# MinieasySens-RS485_V12-Build020.net
KiCad netlist of a schematic drawn in EAGLE
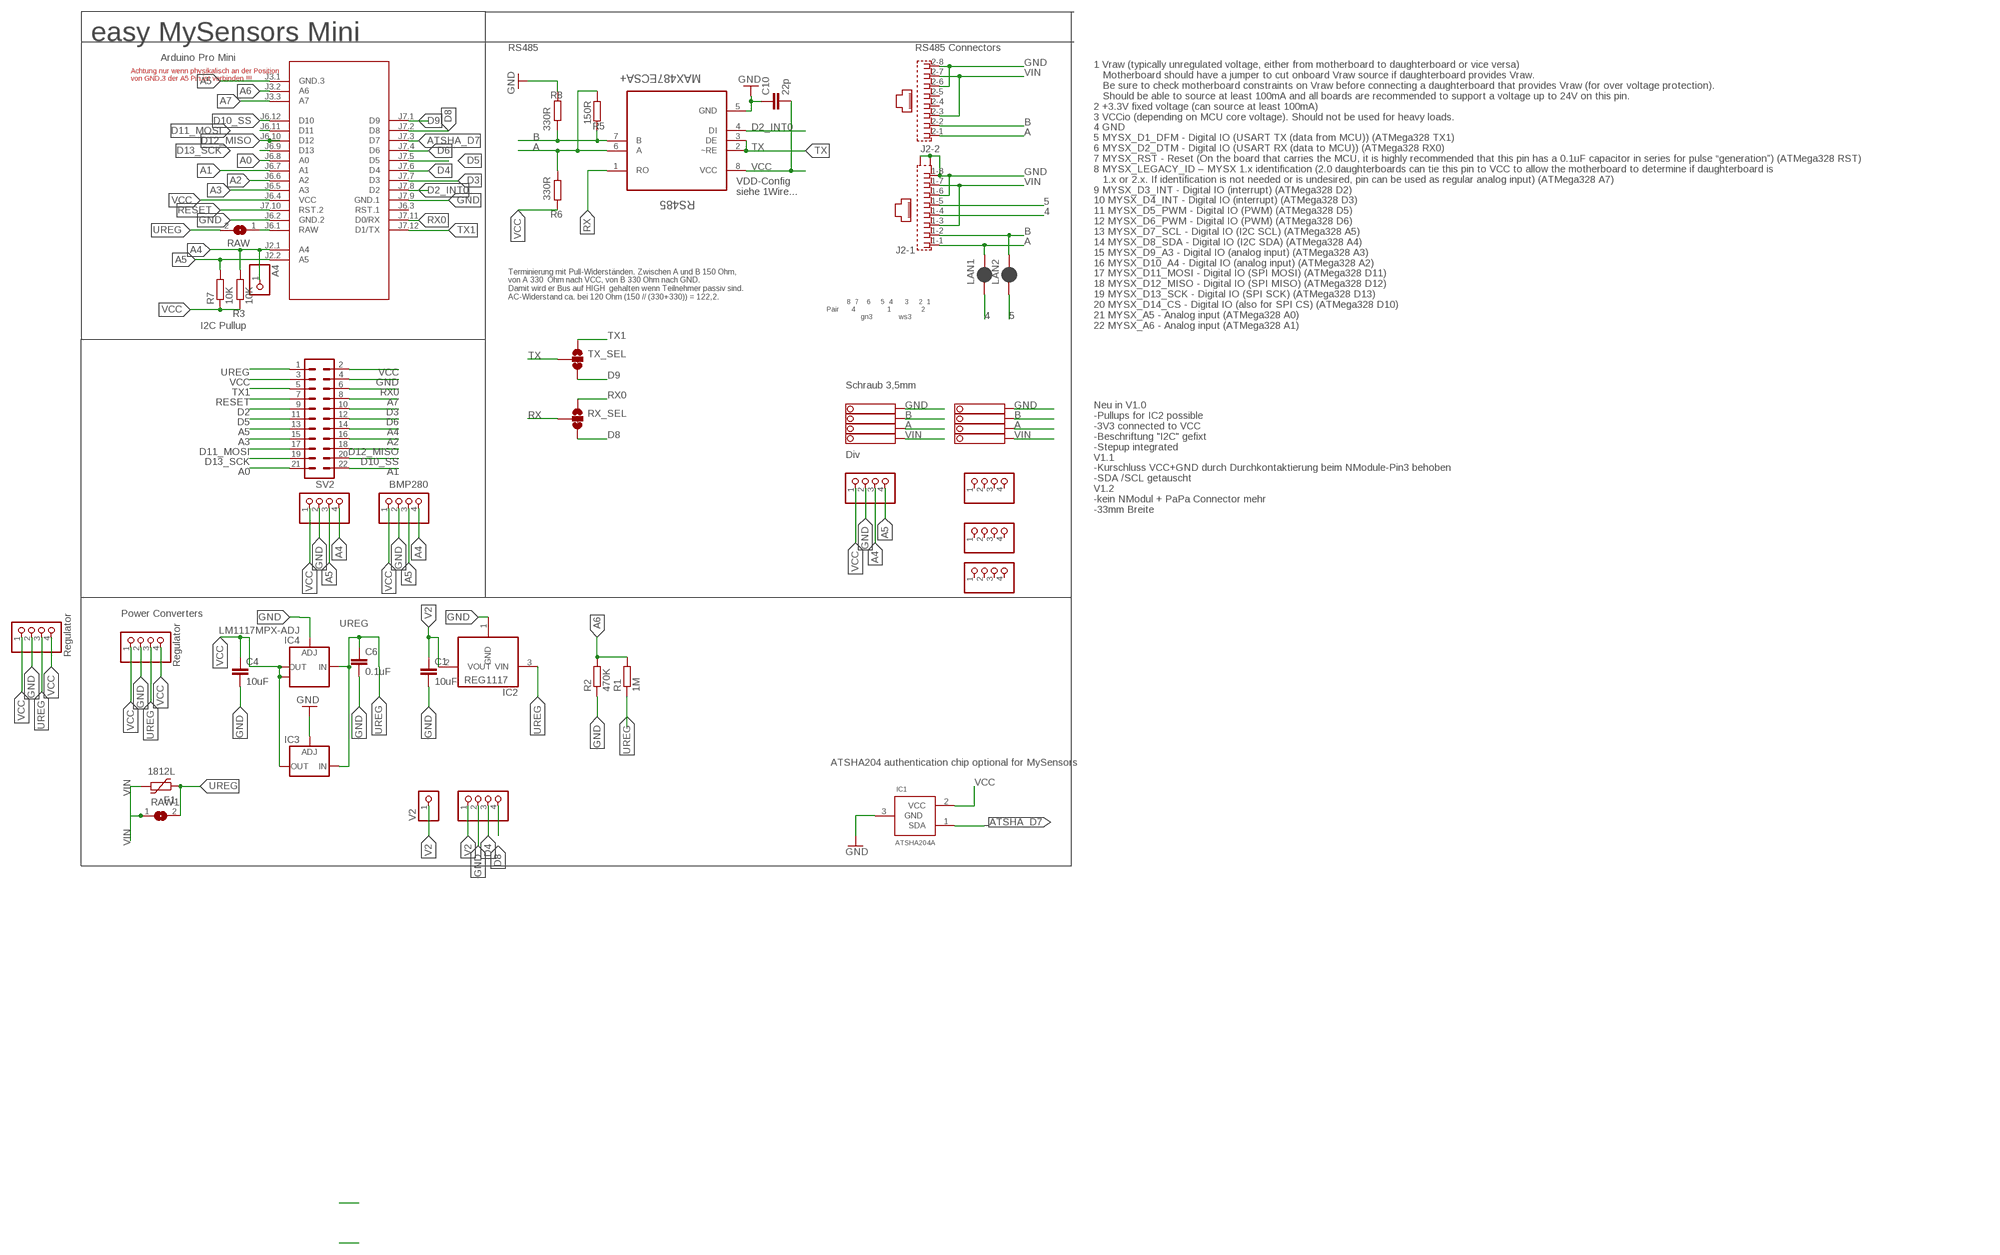
[diagram p0: schematic, sheet 1]

(export (version "E")
  (design (tool "Eeschema 10.0.6"))
  (components
    (comp (ref "A4")
      (value "PINHD-1X1")
      (footprint "eagle-import:1X01")
      (libsource (lib "eagle-import") (part "PINHD-1X1"))
    )
    (comp (ref "BH1750")
      (value "PINHD-1X04_2.54-S")
      (footprint "eagle-import:1X04-S")
      (libsource (lib "eagle-import") (part "PINHD-1X04_2.54-S"))
    )
    (comp (ref "C1")
      (value "10uF")
      (footprint "eagle-import:C1210")
      (libsource (lib "eagle-import") (part "C-EUC1210"))
    )
    (comp (ref "C4")
      (value "10uF")
      (footprint "eagle-import:C1210")
      (libsource (lib "eagle-import") (part "C-EUC1210"))
    )
    (comp (ref "C6")
      (value "0.1uF")
      (footprint "eagle-import:C1206")
      (libsource (lib "eagle-import") (part "C-EUC1206"))
    )
    (comp (ref "C10")
      (value "22p")
      (footprint "eagle-import:C0805")
      (libsource (lib "eagle-import") (part "C-EUC0805"))
    )
    (comp (ref "F1")
      (value "1812L")
      (footprint "eagle-import:1812L")
      (libsource (lib "eagle-import") (part "1812L"))
    )
    (comp (ref "I2C-1")
      (value "PINHD-1X04_2.54-S")
      (footprint "eagle-import:1X04-S")
      (libsource (lib "eagle-import") (part "PINHD-1X04_2.54-S"))
    )
    (comp (ref "I2C-2")
      (value "PINHD-1X04_2.54-S")
      (footprint "eagle-import:1X04-S")
      (libsource (lib "eagle-import") (part "PINHD-1X04_2.54-S"))
    )
    (comp (ref "IC1")
      (value "ATSHA204A")
      (footprint "eagle-import:SOT23")
      (libsource (lib "eagle-import") (part "ATSHA204A"))
    )
    (comp (ref "IC2")
      (value "REG1117")
      (footprint "eagle-import:SOT223")
      (libsource (lib "eagle-import") (part "REG1117"))
    )
    (comp (ref "IC3")
      (value "LD117ADT50TR")
      (footprint "eagle-import:DPACK")
      (libsource (lib "eagle-import") (part "LD117A?DT50TR"))
    )
    (comp (ref "IC4")
      (value "LM1117MPX-ADJ")
      (footprint "eagle-import:SOT223")
      (libsource (lib "eagle-import") (part "LM1117MPX-ADJ"))
    )
    (comp (ref "J2")
      (value "RJ45_2X_NARROW_SHILDPINS_NOCASE")
      (footprint "eagle-import:RJ45_2X_NARROW_SHILDPINS_NOCASE")
      (libsource (lib "eagle-import") (part "RJ45_2X_NARROW_SHILDPINS_NOCASE"))
    )
    (comp (ref "JP1")
      (value "PINHD-1X04_2.54-S")
      (footprint "eagle-import:1X04-S")
      (libsource (lib "eagle-import") (part "PINHD-1X04_2.54-S"))
    )
    (comp (ref "JP2")
      (value "PINHD-1X04_2.54-S")
      (footprint "eagle-import:1X04-S")
      (libsource (lib "eagle-import") (part "PINHD-1X04_2.54-S"))
    )
    (comp (ref "JP4")
      (value "PINHD-1X04_2.54-S")
      (footprint "eagle-import:1X04-S")
      (libsource (lib "eagle-import") (part "PINHD-1X04_2.54-S"))
    )
    (comp (ref "LAN1")
      (value "JUMPER-SMT_2_NC_PASTE_SILK")
      (footprint "eagle-import:SMT-JUMPER_2_NC_PASTE_SILK")
      (libsource (lib "eagle-import") (part "JUMPER-SMT_2_NC_PASTE_SILK"))
    )
    (comp (ref "LAN2")
      (value "JUMPER-SMT_2_NC_PASTE_SILK")
      (footprint "eagle-import:SMT-JUMPER_2_NC_PASTE_SILK")
      (libsource (lib "eagle-import") (part "JUMPER-SMT_2_NC_PASTE_SILK"))
    )
    (comp (ref "M1")
      (value "ARDUINO-PRO-MINI-3.3V#NP")
      (footprint "eagle-import:ARDUINO-PRO-MINI#NP")
      (libsource (lib "eagle-import") (part "ARDUINO-PRO-MINI-#NP3.3V"))
    )
    (comp (ref "R1")
      (value "1M")
      (footprint "eagle-import:R0805")
      (libsource (lib "eagle-import") (part "R-EU_R0805"))
    )
    (comp (ref "R2")
      (value "470K")
      (footprint "eagle-import:R0805")
      (libsource (lib "eagle-import") (part "R-EU_R0805"))
    )
    (comp (ref "R3")
      (value "10K")
      (footprint "eagle-import:R0805")
      (libsource (lib "eagle-import") (part "R-EU_R0805"))
    )
    (comp (ref "R5")
      (value "150R")
      (footprint "eagle-import:R0805")
      (libsource (lib "eagle-import") (part "R-EU_R0805"))
    )
    (comp (ref "R6")
      (value "330R")
      (footprint "eagle-import:R0805")
      (libsource (lib "eagle-import") (part "R-EU_R0805"))
    )
    (comp (ref "R7")
      (value "10K")
      (footprint "eagle-import:R0805")
      (libsource (lib "eagle-import") (part "R-EU_R0805"))
    )
    (comp (ref "R8")
      (value "330R")
      (footprint "eagle-import:R0805")
      (libsource (lib "eagle-import") (part "R-EU_R0805"))
    )
    (comp (ref "RAW") (value "SJ") (footprint "eagle-import:SJ") (libsource (lib "eagle-import") (part "SJ")))
    (comp (ref "RAW1")
      (value "SJ")
      (footprint "eagle-import:SJ")
      (libsource (lib "eagle-import") (part "SJ"))
    )
    (comp (ref "RS485")
      (value "MAX487ECSA+")
      (footprint "eagle-import:SOIC127P600X175-8N")
      (libsource (lib "eagle-import") (part "MAX487ECSA+"))
    )
    (comp (ref "RX_SEL")
      (value "JUMPER-SMT_3_1-NC_TRACE_SILK")
      (footprint "eagle-import:SMT-JUMPER_3_1-NC_TRACE_SILK")
      (libsource (lib "eagle-import") (part "JUMPER-SMT_3_1-NC_TRACE_SILK"))
    )
    (comp (ref "STEPDWN")
      (value "PINHD-1X04_2.54-S")
      (footprint "eagle-import:1X04-S")
      (libsource (lib "eagle-import") (part "PINHD-1X04_2.54-S"))
    )
    (comp (ref "STEPDWN1")
      (value "PINHD-1X04_2.54-S")
      (footprint "eagle-import:1X04-S")
      (libsource (lib "eagle-import") (part "PINHD-1X04_2.54-S"))
    )
    (comp (ref "SV2")
      (value "MA11-2")
      (footprint "eagle-import:MA11-2")
      (libsource (lib "eagle-import") (part "MA11-2"))
    )
    (comp (ref "TX_SEL")
      (value "JUMPER-SMT_3_1-NC_TRACE_SILK")
      (footprint "eagle-import:SMT-JUMPER_3_1-NC_TRACE_SILK")
      (libsource (lib "eagle-import") (part "JUMPER-SMT_3_1-NC_TRACE_SILK"))
    )
    (comp (ref "V2")
      (value "PINHD-1X1")
      (footprint "eagle-import:1X01")
      (libsource (lib "eagle-import") (part "PINHD-1X1"))
    )
    (comp (ref "V2-")
      (value "PINHD-1X04_2.54-S")
      (footprint "eagle-import:1X04-S")
      (libsource (lib "eagle-import") (part "PINHD-1X04_2.54-S"))
    )
    (comp (ref "X1")
      (value "1751264")
      (footprint "eagle-import:1751264")
      (libsource (lib "eagle-import") (part "1751264"))
    )
    (comp (ref "X4")
      (value "1751264")
      (footprint "eagle-import:1751264")
      (libsource (lib "eagle-import") (part "1751264"))
    )
  )
  (nets
    (net (code "1") (name "/4") (class "Default")
      (node (ref "J2") (pin "1-4") (pinfunction "4_1-4") (pintype "passive"))
      (node (ref "LAN1") (pin "1") (pinfunction "1_1") (pintype "passive"))
    )
    (net (code "2") (name "/5") (class "Default")
      (node (ref "J2") (pin "1-5") (pinfunction "5_1-5") (pintype "passive"))
      (node (ref "LAN2") (pin "1") (pinfunction "1_1") (pintype "passive"))
    )
    (net (code "3") (name "/A") (class "Default")
      (node (ref "J2") (pin "1-1") (pinfunction "1_1-1") (pintype "passive"))
      (node (ref "J2") (pin "2-1") (pinfunction "1_2-1") (pintype "passive"))
      (node (ref "LAN1") (pin "2") (pinfunction "2_2") (pintype "passive"))
      (node (ref "R5") (pin "1") (pinfunction "1_1") (pintype "passive"))
      (node (ref "R6") (pin "2") (pinfunction "2_2") (pintype "passive"))
      (node (ref "RS485") (pin "6") (pinfunction "A_6") (pintype "bidirectional"))
      (node (ref "X1") (pin "2") (pinfunction "K_2") (pintype "passive"))
      (node (ref "X4") (pin "2") (pinfunction "K_2") (pintype "passive"))
    )
    (net (code "4") (name "/B") (class "Default")
      (node (ref "J2") (pin "1-2") (pinfunction "2_1-2") (pintype "passive"))
      (node (ref "J2") (pin "2-2") (pinfunction "2_2-2") (pintype "passive"))
      (node (ref "LAN2") (pin "2") (pinfunction "2_2") (pintype "passive"))
      (node (ref "R5") (pin "2") (pinfunction "2_2") (pintype "passive"))
      (node (ref "R8") (pin "1") (pinfunction "1_1") (pintype "passive"))
      (node (ref "RS485") (pin "7") (pinfunction "B_7") (pintype "bidirectional"))
      (node (ref "X1") (pin "3") (pinfunction "K_3") (pintype "passive"))
      (node (ref "X4") (pin "3") (pinfunction "K_3") (pintype "passive"))
    )
    (net (code "5") (name "/D2") (class "Default")
      (node (ref "SV2") (pin "9") (pinfunction "9_9") (pintype "passive"))
    )
    (net (code "6") (name "/VIN") (class "Default")
      (node (ref "F1") (pin "P$2") (pinfunction "2_P$2") (pintype "passive"))
      (node (ref "J2") (pin "1-3") (pinfunction "3_1-3") (pintype "passive"))
      (node (ref "J2") (pin "1-7") (pinfunction "7_1-7") (pintype "passive"))
      (node (ref "J2") (pin "2-3") (pinfunction "3_2-3") (pintype "passive"))
      (node (ref "J2") (pin "2-7") (pinfunction "7_2-7") (pintype "passive"))
      (node (ref "RAW1") (pin "1") (pinfunction "1_1") (pintype "passive"))
      (node (ref "X1") (pin "1") (pinfunction "K_1") (pintype "passive"))
      (node (ref "X4") (pin "1") (pinfunction "K_1") (pintype "passive"))
    )
    (net (code "7") (name "A0") (class "Default")
      (node (ref "M1") (pin "J6.8") (pinfunction "A0_J6.8") (pintype "bidirectional"))
      (node (ref "SV2") (pin "21") (pinfunction "21_21") (pintype "passive"))
    )
    (net (code "8") (name "A1") (class "Default")
      (node (ref "M1") (pin "J6.7") (pinfunction "A1_J6.7") (pintype "bidirectional"))
      (node (ref "SV2") (pin "22") (pinfunction "22_22") (pintype "passive"))
    )
    (net (code "9") (name "A2") (class "Default")
      (node (ref "M1") (pin "J6.6") (pinfunction "A2_J6.6") (pintype "bidirectional"))
      (node (ref "SV2") (pin "16") (pinfunction "16_16") (pintype "passive"))
    )
    (net (code "10") (name "A3") (class "Default")
      (node (ref "M1") (pin "J6.5") (pinfunction "A3_J6.5") (pintype "bidirectional"))
      (node (ref "SV2") (pin "15") (pinfunction "15_15") (pintype "passive"))
    )
    (net (code "11") (name "A4") (class "Default")
      (node (ref "A4") (pin "1") (pinfunction "1_1") (pintype "passive"))
      (node (ref "BH1750") (pin "4") (pinfunction "4_4") (pintype "passive"))
      (node (ref "I2C-1") (pin "4") (pinfunction "4_4") (pintype "passive"))
      (node (ref "I2C-2") (pin "3") (pinfunction "3_3") (pintype "passive"))
      (node (ref "M1") (pin "J2.1") (pinfunction "A4_J2.1") (pintype "bidirectional"))
      (node (ref "R3") (pin "2") (pinfunction "2_2") (pintype "passive"))
      (node (ref "SV2") (pin "14") (pinfunction "14_14") (pintype "passive"))
    )
    (net (code "12") (name "A5") (class "Default")
      (node (ref "BH1750") (pin "3") (pinfunction "3_3") (pintype "passive"))
      (node (ref "I2C-1") (pin "3") (pinfunction "3_3") (pintype "passive"))
      (node (ref "I2C-2") (pin "4") (pinfunction "4_4") (pintype "passive"))
      (node (ref "M1") (pin "J2.2") (pinfunction "A5_J2.2") (pintype "bidirectional"))
      (node (ref "M1") (pin "J3.1") (pinfunction "GND.3_J3.1") (pintype "bidirectional"))
      (node (ref "R7") (pin "2") (pinfunction "2_2") (pintype "passive"))
      (node (ref "SV2") (pin "13") (pinfunction "13_13") (pintype "passive"))
    )
    (net (code "13") (name "A6") (class "Default")
      (node (ref "M1") (pin "J3.2") (pinfunction "A6_J3.2") (pintype "bidirectional"))
      (node (ref "R1") (pin "2") (pinfunction "2_2") (pintype "passive"))
      (node (ref "R2") (pin "2") (pinfunction "2_2") (pintype "passive"))
    )
    (net (code "14") (name "A7") (class "Default")
      (node (ref "M1") (pin "J3.3") (pinfunction "A7_J3.3") (pintype "bidirectional"))
      (node (ref "SV2") (pin "8") (pinfunction "8_8") (pintype "passive"))
    )
    (net (code "15") (name "ATSHA_D7") (class "Default")
      (node (ref "IC1") (pin "1") (pinfunction "SDA_1") (pintype "bidirectional"))
      (node (ref "M1") (pin "J7.3") (pinfunction "D7_J7.3") (pintype "bidirectional"))
    )
    (net (code "16") (name "D2_INT0") (class "Default")
      (node (ref "M1") (pin "J7.8") (pinfunction "D2_J7.8") (pintype "bidirectional"))
      (node (ref "RS485") (pin "4") (pinfunction "DI_4") (pintype "input"))
    )
    (net (code "17") (name "D3") (class "Default")
      (node (ref "M1") (pin "J7.7") (pinfunction "D3_J7.7") (pintype "bidirectional"))
      (node (ref "SV2") (pin "10") (pinfunction "10_10") (pintype "passive"))
    )
    (net (code "18") (name "D4") (class "Default")
      (node (ref "M1") (pin "J7.6") (pinfunction "D4_J7.6") (pintype "bidirectional"))
      (node (ref "V2-") (pin "3") (pinfunction "3_3") (pintype "passive"))
    )
    (net (code "19") (name "D5") (class "Default")
      (node (ref "M1") (pin "J7.5") (pinfunction "D5_J7.5") (pintype "bidirectional"))
      (node (ref "SV2") (pin "11") (pinfunction "11_11") (pintype "passive"))
    )
    (net (code "20") (name "D6") (class "Default")
      (node (ref "M1") (pin "J7.4") (pinfunction "D6_J7.4") (pintype "bidirectional"))
      (node (ref "SV2") (pin "12") (pinfunction "12_12") (pintype "passive"))
    )
    (net (code "21") (name "D8") (class "Default")
      (node (ref "M1") (pin "J7.2") (pinfunction "D8_J7.2") (pintype "bidirectional"))
      (node (ref "RX_SEL") (pin "3") (pinfunction "3_3") (pintype "passive"))
      (node (ref "V2-") (pin "4") (pinfunction "4_4") (pintype "passive"))
    )
    (net (code "22") (name "D9") (class "Default")
      (node (ref "M1") (pin "J7.1") (pinfunction "D9_J7.1") (pintype "bidirectional"))
      (node (ref "TX_SEL") (pin "3") (pinfunction "3_3") (pintype "passive"))
    )
    (net (code "23") (name "D10_SS") (class "Default")
      (node (ref "M1") (pin "J6.12") (pinfunction "D10_J6.12") (pintype "bidirectional"))
      (node (ref "SV2") (pin "20") (pinfunction "20_20") (pintype "passive"))
    )
    (net (code "24") (name "D11_MOSI") (class "Default")
      (node (ref "M1") (pin "J6.11") (pinfunction "D11_J6.11") (pintype "bidirectional"))
      (node (ref "SV2") (pin "17") (pinfunction "17_17") (pintype "passive"))
    )
    (net (code "25") (name "D12_MISO") (class "Default")
      (node (ref "M1") (pin "J6.10") (pinfunction "D12_J6.10") (pintype "bidirectional"))
      (node (ref "SV2") (pin "18") (pinfunction "18_18") (pintype "passive"))
    )
    (net (code "26") (name "D13_SCK") (class "Default")
      (node (ref "M1") (pin "J6.9") (pinfunction "D13_J6.9") (pintype "bidirectional"))
      (node (ref "SV2") (pin "19") (pinfunction "19_19") (pintype "passive"))
    )
    (net (code "27") (name "GND") (class "Default")
      (node (ref "BH1750") (pin "2") (pinfunction "2_2") (pintype "passive"))
      (node (ref "C1") (pin "2") (pinfunction "2_2") (pintype "passive"))
      (node (ref "C10") (pin "1") (pinfunction "1_1") (pintype "passive"))
      (node (ref "C4") (pin "2") (pinfunction "2_2") (pintype "passive"))
      (node (ref "C6") (pin "2") (pinfunction "2_2") (pintype "passive"))
      (node (ref "I2C-1") (pin "2") (pinfunction "2_2") (pintype "passive"))
      (node (ref "I2C-2") (pin "2") (pinfunction "2_2") (pintype "passive"))
      (node (ref "IC1") (pin "3") (pinfunction "GND_3") (pintype "bidirectional"))
      (node (ref "IC2") (pin "1") (pinfunction "GND_1") (pintype "power_in"))
      (node (ref "IC3") (pin "1") (pinfunction "ADJ_1") (pintype "input"))
      (node (ref "IC4") (pin "1") (pinfunction "ADJ_1") (pintype "input"))
      (node (ref "J2") (pin "1-6") (pinfunction "6_1-6") (pintype "passive"))
      (node (ref "J2") (pin "1-8") (pinfunction "8_1-8") (pintype "passive"))
      (node (ref "J2") (pin "2-6") (pinfunction "6_2-6") (pintype "passive"))
      (node (ref "J2") (pin "2-8") (pinfunction "8_2-8") (pintype "passive"))
      (node (ref "J2") (pin "G1") (pinfunction "S1_G1") (pintype "passive"))
      (node (ref "J2") (pin "G3") (pinfunction "S2_G3") (pintype "passive"))
      (node (ref "M1") (pin "J6.2") (pinfunction "GND.2_J6.2") (pintype "power_in"))
      (node (ref "M1") (pin "J7.9") (pinfunction "GND.1_J7.9") (pintype "power_in"))
      (node (ref "R2") (pin "1") (pinfunction "1_1") (pintype "passive"))
      (node (ref "R8") (pin "2") (pinfunction "2_2") (pintype "passive"))
      (node (ref "RS485") (pin "5") (pinfunction "GND_5") (pintype "passive"))
      (node (ref "STEPDWN") (pin "2") (pinfunction "2_2") (pintype "passive"))
      (node (ref "STEPDWN1") (pin "2") (pinfunction "2_2") (pintype "passive"))
      (node (ref "SV2") (pin "4") (pinfunction "4_4") (pintype "passive"))
      (node (ref "V2-") (pin "2") (pinfunction "2_2") (pintype "passive"))
      (node (ref "X1") (pin "4") (pinfunction "K_4") (pintype "passive"))
      (node (ref "X4") (pin "4") (pinfunction "K_4") (pintype "passive"))
    )
    (net (code "28") (name "Net-(M1-RAW)") (class "Default")
      (node (ref "M1") (pin "J6.1") (pinfunction "RAW_J6.1") (pintype "power_in"))
      (node (ref "RAW") (pin "1") (pinfunction "1_1") (pintype "passive"))
    )
    (net (code "29") (name "RESET") (class "Default")
      (node (ref "M1") (pin "J7.10") (pinfunction "RST.2_J7.10") (pintype "bidirectional"))
      (node (ref "SV2") (pin "7") (pinfunction "7_7") (pintype "passive"))
    )
    (net (code "30") (name "RX") (class "Default")
      (node (ref "RS485") (pin "1") (pinfunction "RO_1") (pintype "output"))
      (node (ref "RX_SEL") (pin "2") (pinfunction "2_2") (pintype "passive"))
    )
    (net (code "31") (name "RX0") (class "Default")
      (node (ref "M1") (pin "J7.11") (pinfunction "D0/RX_J7.11") (pintype "bidirectional"))
      (node (ref "RX_SEL") (pin "1") (pinfunction "1_1") (pintype "passive"))
      (node (ref "SV2") (pin "6") (pinfunction "6_6") (pintype "passive"))
    )
    (net (code "32") (name "TX") (class "Default")
      (node (ref "RS485") (pin "2") (pinfunction "~{RE}_2") (pintype "input"))
      (node (ref "RS485") (pin "3") (pinfunction "DE_3") (pintype "input"))
      (node (ref "TX_SEL") (pin "2") (pinfunction "2_2") (pintype "passive"))
    )
    (net (code "33") (name "TX1") (class "Default")
      (node (ref "M1") (pin "J7.12") (pinfunction "D1/TX_J7.12") (pintype "bidirectional"))
      (node (ref "SV2") (pin "5") (pinfunction "5_5") (pintype "passive"))
      (node (ref "TX_SEL") (pin "1") (pinfunction "1_1") (pintype "passive"))
    )
    (net (code "34") (name "UREG") (class "Default")
      (node (ref "C6") (pin "1") (pinfunction "1_1") (pintype "passive"))
      (node (ref "F1") (pin "P$1") (pinfunction "1_P$1") (pintype "passive"))
      (node (ref "IC2") (pin "3") (pinfunction "VIN_3") (pintype "input"))
      (node (ref "IC3") (pin "3") (pinfunction "IN_3") (pintype "input"))
      (node (ref "IC4") (pin "3") (pinfunction "IN_3") (pintype "input"))
      (node (ref "R1") (pin "1") (pinfunction "1_1") (pintype "passive"))
      (node (ref "RAW") (pin "2") (pinfunction "2_2") (pintype "passive"))
      (node (ref "RAW1") (pin "2") (pinfunction "2_2") (pintype "passive"))
      (node (ref "STEPDWN") (pin "3") (pinfunction "3_3") (pintype "passive"))
      (node (ref "STEPDWN1") (pin "3") (pinfunction "3_3") (pintype "passive"))
      (node (ref "SV2") (pin "1") (pinfunction "1_1") (pintype "passive"))
    )
    (net (code "35") (name "V2") (class "Default")
      (node (ref "C1") (pin "1") (pinfunction "1_1") (pintype "passive"))
      (node (ref "IC2") (pin "2") (pinfunction "VOUT_2") (pintype "output"))
      (node (ref "V2") (pin "1") (pinfunction "1_1") (pintype "passive"))
      (node (ref "V2-") (pin "1") (pinfunction "1_1") (pintype "passive"))
    )
    (net (code "36") (name "VCC") (class "Default")
      (node (ref "BH1750") (pin "1") (pinfunction "1_1") (pintype "passive"))
      (node (ref "C10") (pin "2") (pinfunction "2_2") (pintype "passive"))
      (node (ref "C4") (pin "1") (pinfunction "1_1") (pintype "passive"))
      (node (ref "I2C-1") (pin "1") (pinfunction "1_1") (pintype "passive"))
      (node (ref "I2C-2") (pin "1") (pinfunction "1_1") (pintype "passive"))
      (node (ref "IC1") (pin "2") (pinfunction "VCC_2") (pintype "bidirectional"))
      (node (ref "IC3") (pin "4") (pinfunction "OUT_4") (pintype "passive"))
      (node (ref "IC4") (pin "2") (pinfunction "OUT_2") (pintype "passive"))
      (node (ref "IC4") (pin "TAB") (pinfunction "OUT1_TAB") (pintype "passive"))
      (node (ref "M1") (pin "J6.4") (pinfunction "VCC_J6.4") (pintype "power_in"))
      (node (ref "R3") (pin "1") (pinfunction "1_1") (pintype "passive"))
      (node (ref "R6") (pin "1") (pinfunction "1_1") (pintype "passive"))
      (node (ref "R7") (pin "1") (pinfunction "1_1") (pintype "passive"))
      (node (ref "RS485") (pin "8") (pinfunction "VCC_8") (pintype "power_in"))
      (node (ref "STEPDWN") (pin "1") (pinfunction "1_1") (pintype "passive"))
      (node (ref "STEPDWN") (pin "4") (pinfunction "4_4") (pintype "passive"))
      (node (ref "STEPDWN1") (pin "1") (pinfunction "1_1") (pintype "passive"))
      (node (ref "STEPDWN1") (pin "4") (pinfunction "4_4") (pintype "passive"))
      (node (ref "SV2") (pin "2") (pinfunction "2_2") (pintype "passive"))
      (node (ref "SV2") (pin "3") (pinfunction "3_3") (pintype "passive"))
    )
    (net (code "37") (name "unconnected-(J2B-4-Pad2-4)") (class "Default")
      (node (ref "J2") (pin "2-4") (pinfunction "4_2-4") (pintype "passive"))
    )
    (net (code "38") (name "unconnected-(J2B-5-Pad2-5)") (class "Default")
      (node (ref "J2") (pin "2-5") (pinfunction "5_2-5") (pintype "passive"))
    )
    (net (code "39") (name "unconnected-(JP1-Pad1)") (class "Default")
      (node (ref "JP1") (pin "1") (pinfunction "1_1") (pintype "passive"))
    )
    (net (code "40") (name "unconnected-(JP1-Pad2)") (class "Default")
      (node (ref "JP1") (pin "2") (pinfunction "2_2") (pintype "passive"))
    )
    (net (code "41") (name "unconnected-(JP1-Pad3)") (class "Default")
      (node (ref "JP1") (pin "3") (pinfunction "3_3") (pintype "passive"))
    )
    (net (code "42") (name "unconnected-(JP1-Pad4)") (class "Default")
      (node (ref "JP1") (pin "4") (pinfunction "4_4") (pintype "passive"))
    )
    (net (code "43") (name "unconnected-(JP2-Pad1)") (class "Default")
      (node (ref "JP2") (pin "1") (pinfunction "1_1") (pintype "passive"))
    )
    (net (code "44") (name "unconnected-(JP2-Pad2)") (class "Default")
      (node (ref "JP2") (pin "2") (pinfunction "2_2") (pintype "passive"))
    )
    (net (code "45") (name "unconnected-(JP2-Pad3)") (class "Default")
      (node (ref "JP2") (pin "3") (pinfunction "3_3") (pintype "passive"))
    )
    (net (code "46") (name "unconnected-(JP2-Pad4)") (class "Default")
      (node (ref "JP2") (pin "4") (pinfunction "4_4") (pintype "passive"))
    )
    (net (code "47") (name "unconnected-(JP4-Pad1)") (class "Default")
      (node (ref "JP4") (pin "1") (pinfunction "1_1") (pintype "passive"))
    )
    (net (code "48") (name "unconnected-(JP4-Pad2)") (class "Default")
      (node (ref "JP4") (pin "2") (pinfunction "2_2") (pintype "passive"))
    )
    (net (code "49") (name "unconnected-(JP4-Pad3)") (class "Default")
      (node (ref "JP4") (pin "3") (pinfunction "3_3") (pintype "passive"))
    )
    (net (code "50") (name "unconnected-(JP4-Pad4)") (class "Default")
      (node (ref "JP4") (pin "4") (pinfunction "4_4") (pintype "passive"))
    )
    (net (code "51") (name "unconnected-(M1-RST.1-PadJ6.3)") (class "Default")
      (node (ref "M1") (pin "J6.3") (pinfunction "RST.1_J6.3") (pintype "bidirectional"))
    )
  )
)
